# SAMV71_Xplained_Ultra_Memory.net
KiCad netlist of a schematic drawn in Altium Designer
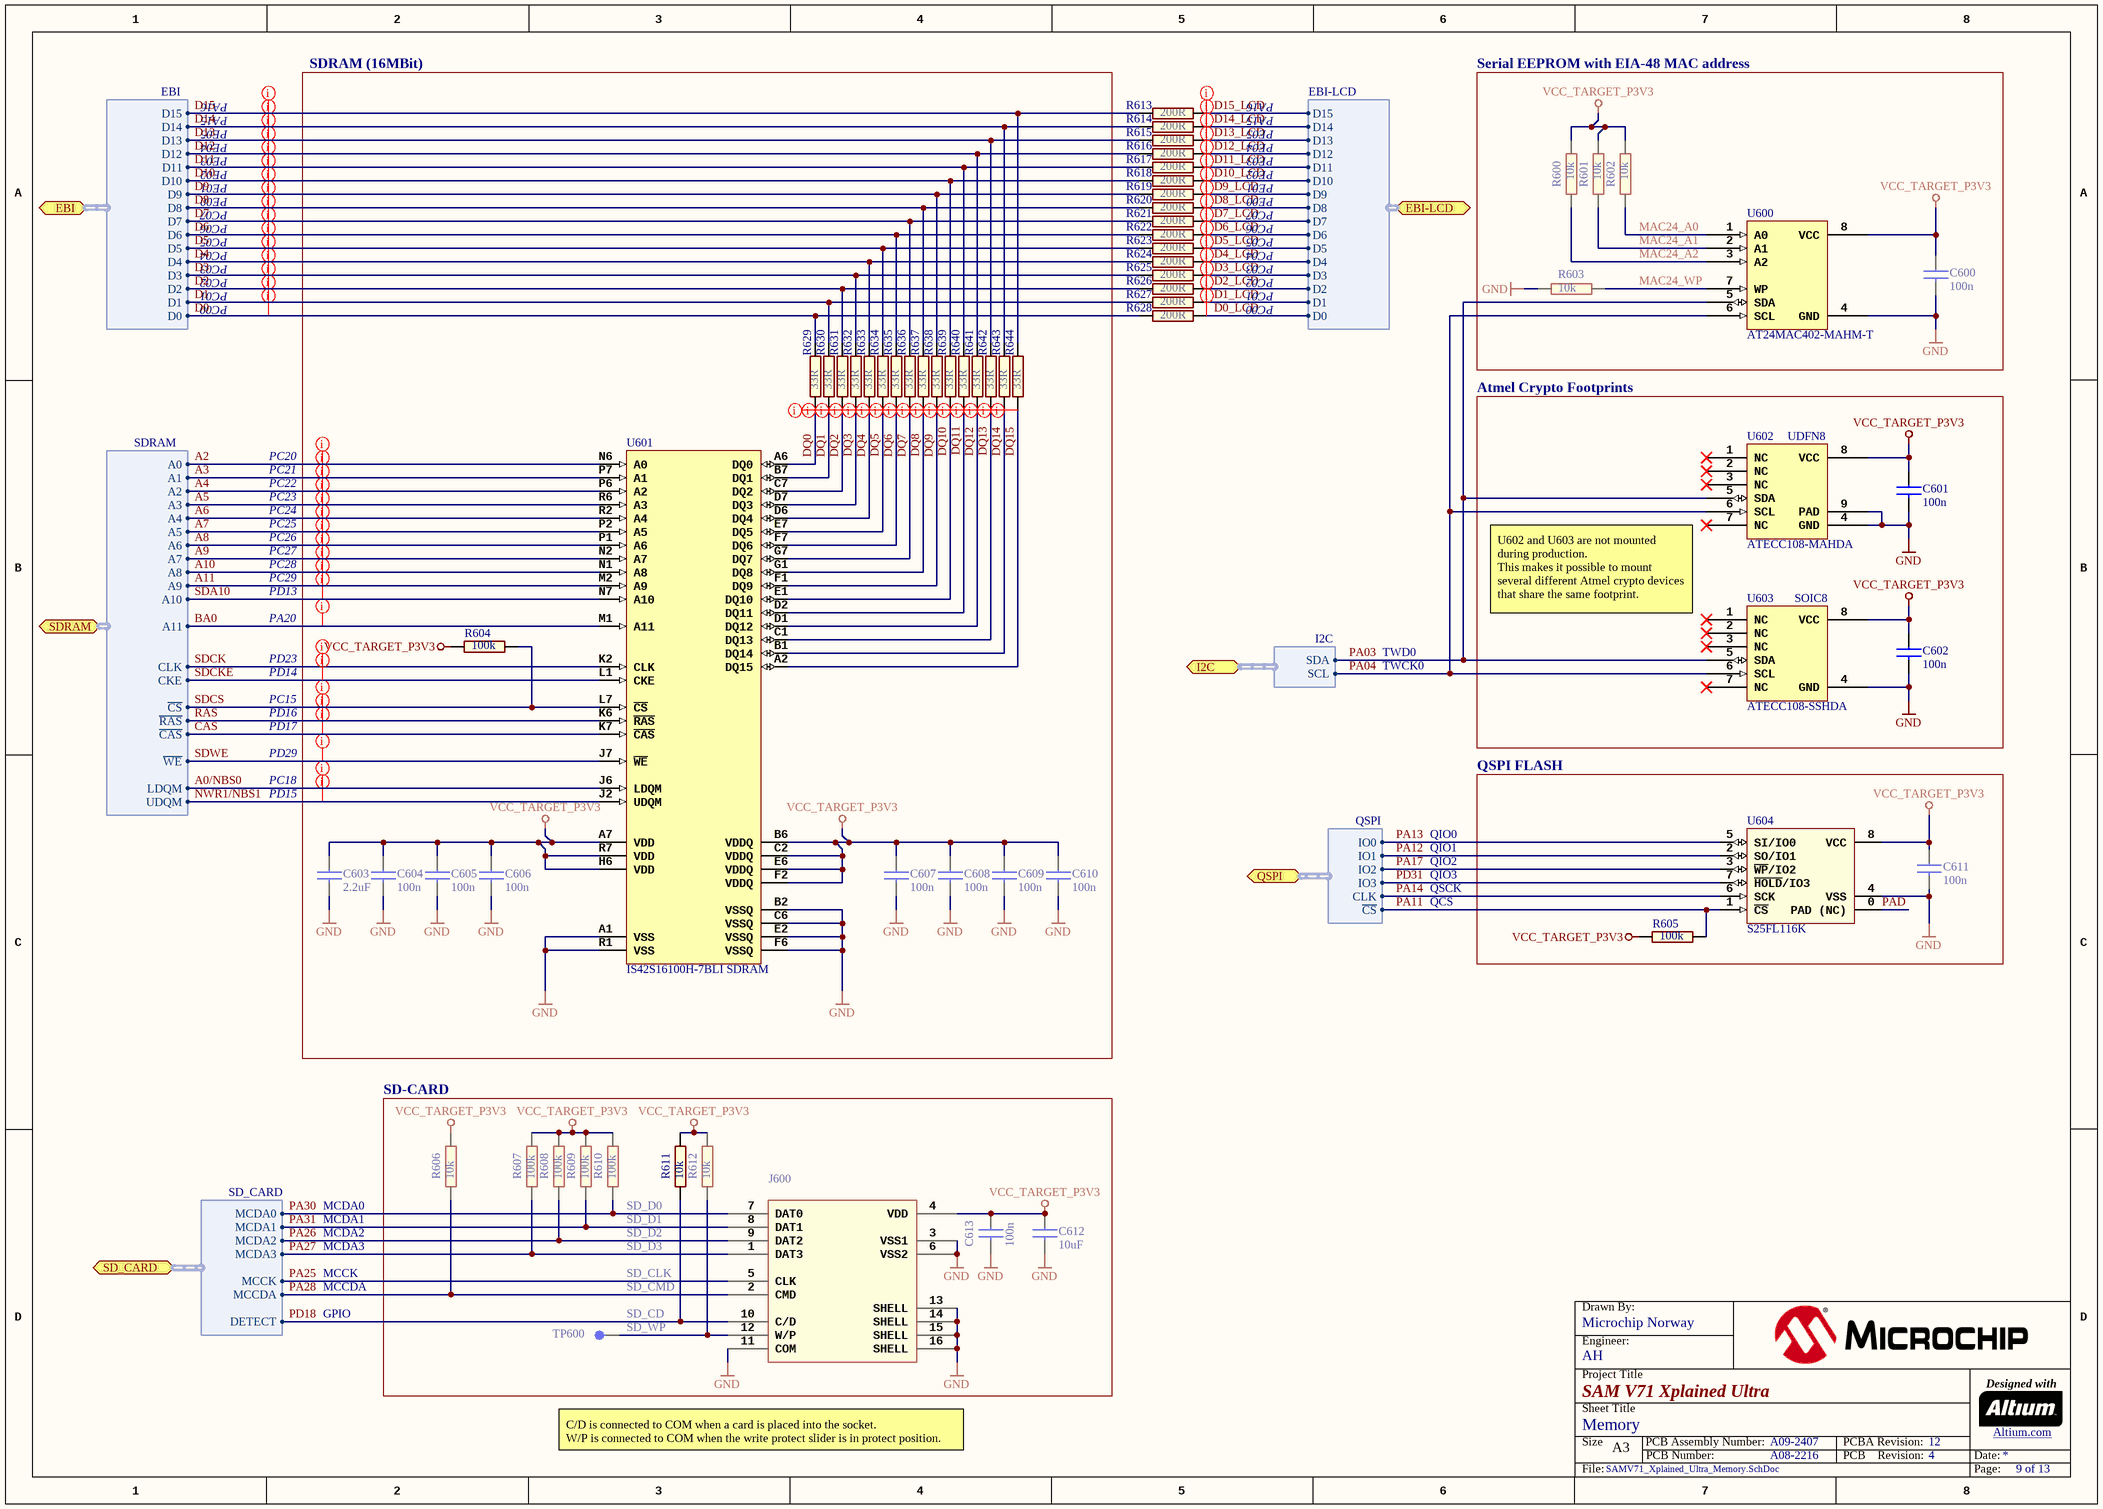
[diagram p0: SAMV71_Xplained_Ultra_Memory.SchDoc]

(export (version "E")
  (design (tool "Eeschema 10.0.6"))
  (components
    (comp (ref "C600")
      (value "100n")
      (footprint "AP1-00001")
      (description "Ceramic capacitor, SMD 0402, X7R, 16V, +/-10%")
      (fields (field (name "TOLERANCE") "16V, +/-10%") (field (name "MANUFACTURER") "Kemet"))
      (libsource (lib "AltiumDbLib") (part "CAP-NONPOL"))
    )
    (comp (ref "C601")
      (value "100n")
      (footprint "AP1-00001")
      (description "Ceramic capacitor, SMD 0402, X7R, 16V, +/-10%")
      (fields (field (name "TOLERANCE") "16V, +/-10%") (field (name "MANUFACTURER") "Kemet"))
      (libsource (lib "AltiumDbLib") (part "CAP-NONPOL"))
    )
    (comp (ref "C602")
      (value "100n")
      (footprint "AP1-00001")
      (description "Ceramic capacitor, SMD 0402, X7R, 16V, +/-10%")
      (fields (field (name "TOLERANCE") "16V, +/-10%") (field (name "MANUFACTURER") "Kemet"))
      (libsource (lib "AltiumDbLib") (part "CAP-NONPOL"))
    )
    (comp (ref "C603")
      (value "2.2uF")
      (footprint "AP1-00053")
      (description "Ceramic capacitor, SMD 0402, X5R, 6.3V, +/-20%")
      (fields (field (name "TOLERANCE") "Â±20%") (field (name "MANUFACTURER") "Kemet"))
      (libsource (lib "AltiumDbLib") (part "CAP-NONPOL"))
    )
    (comp (ref "C604")
      (value "100n")
      (footprint "AP1-00053")
      (description "Ceramic capacitor, SMD 0402, X7R, 16V, +/-10%")
      (fields (field (name "TOLERANCE") "16V, +/-10%") (field (name "MANUFACTURER") "Kemet"))
      (libsource (lib "AltiumDbLib") (part "CAP-NONPOL"))
    )
    (comp (ref "C605")
      (value "100n")
      (footprint "AP1-00053")
      (description "Ceramic capacitor, SMD 0402, X7R, 16V, +/-10%")
      (fields (field (name "TOLERANCE") "16V, +/-10%") (field (name "MANUFACTURER") "Kemet"))
      (libsource (lib "AltiumDbLib") (part "CAP-NONPOL"))
    )
    (comp (ref "C606")
      (value "100n")
      (footprint "AP1-00053")
      (description "Ceramic capacitor, SMD 0402, X7R, 16V, +/-10%")
      (fields (field (name "TOLERANCE") "16V, +/-10%") (field (name "MANUFACTURER") "Kemet"))
      (libsource (lib "AltiumDbLib") (part "CAP-NONPOL"))
    )
    (comp (ref "C607")
      (value "100n")
      (footprint "AP1-00053")
      (description "Ceramic capacitor, SMD 0402, X7R, 16V, +/-10%")
      (fields (field (name "TOLERANCE") "16V, +/-10%") (field (name "MANUFACTURER") "Kemet"))
      (libsource (lib "AltiumDbLib") (part "CAP-NONPOL"))
    )
    (comp (ref "C608")
      (value "100n")
      (footprint "AP1-00053")
      (description "Ceramic capacitor, SMD 0402, X7R, 16V, +/-10%")
      (fields (field (name "TOLERANCE") "16V, +/-10%") (field (name "MANUFACTURER") "Kemet"))
      (libsource (lib "AltiumDbLib") (part "CAP-NONPOL"))
    )
    (comp (ref "C609")
      (value "100n")
      (footprint "AP1-00053")
      (description "Ceramic capacitor, SMD 0402, X7R, 16V, +/-10%")
      (fields (field (name "TOLERANCE") "16V, +/-10%") (field (name "MANUFACTURER") "Kemet"))
      (libsource (lib "AltiumDbLib") (part "CAP-NONPOL"))
    )
    (comp (ref "C610")
      (value "100n")
      (footprint "AP1-00053")
      (description "Ceramic capacitor, SMD 0402, X7R, 16V, +/-10%")
      (fields (field (name "TOLERANCE") "16V, +/-10%") (field (name "MANUFACTURER") "Kemet"))
      (libsource (lib "AltiumDbLib") (part "CAP-NONPOL"))
    )
    (comp (ref "C611")
      (value "100n")
      (footprint "AP1-00001")
      (description "Ceramic capacitor, SMD 0402, X7R, 16V, +/-10%")
      (fields (field (name "TOLERANCE") "16V, +/-10%") (field (name "MANUFACTURER") "Kemet"))
      (libsource (lib "AltiumDbLib") (part "CAP-NONPOL"))
    )
    (comp (ref "C612")
      (value "10uF")
      (footprint "AP1-00041")
      (description "Ceramic capacitor, SMD 0805, X5R, 10V, 10 %, (de19441)")
      (fields (field (name "TOLERANCE") "10%") (field (name "MANUFACTURER") "Murata"))
      (libsource (lib "AltiumDbLib") (part "CAP-NONPOL"))
    )
    (comp (ref "C613")
      (value "100n")
      (footprint "AP1-00001")
      (description "Ceramic capacitor, SMD 0402, X7R, 16V, +/-10%")
      (fields (field (name "TOLERANCE") "16V, +/-10%") (field (name "MANUFACTURER") "Kemet"))
      (libsource (lib "AltiumDbLib") (part "CAP-NONPOL"))
    )
    (comp (ref "J600")
      (value "~")
      (footprint "AP8-00377")
      (description "SD/MMC socket, 2.7mm, push-push, SMD")
      (fields
        (field (name "MANUFACTURER") "Kyocera-elco")
        (field (name "MPN") "KYOCERA - 14 5738 009 220 859+")
      )
      (libsource (lib "AltiumDbLib") (part "SD_MMC"))
    )
    (comp (ref "R600")
      (value "10k")
      (footprint "AP2-00000")
      (description "Thick film resistor, SMD 0402, 1/16W, 1%")
      (fields (field (name "TOLERANCE") "1 %") (field (name "MANUFACTURER") "vishay"))
      (libsource (lib "AltiumDbLib") (part "R2"))
    )
    (comp (ref "R601")
      (value "10k")
      (footprint "AP2-00000")
      (description "Thick film resistor, SMD 0402, 1/16W, 1%")
      (fields (field (name "TOLERANCE") "1 %") (field (name "MANUFACTURER") "vishay"))
      (libsource (lib "AltiumDbLib") (part "R2"))
    )
    (comp (ref "R602")
      (value "10k")
      (footprint "AP2-00000")
      (description "Thick film resistor, SMD 0402, 1/16W, 1%")
      (fields (field (name "TOLERANCE") "1 %") (field (name "MANUFACTURER") "vishay"))
      (libsource (lib "AltiumDbLib") (part "R2"))
    )
    (comp (ref "R603")
      (value "10k")
      (footprint "AP2-00000")
      (description "Thick film resistor, SMD 0402, 1/16W, 1%")
      (fields (field (name "TOLERANCE") "1 %") (field (name "MANUFACTURER") "vishay"))
      (libsource (lib "") (part "R2_2"))
    )
    (comp (ref "R604")
      (value "100k")
      (footprint "AP2-00000")
      (description "Thick film resistor, SMD 0402, 1/16W, 1%")
      (fields (field (name "TOLERANCE") "1 %") (field (name "MANUFACTURER") "ASJ"))
      (libsource (lib "") (part "R2_2"))
    )
    (comp (ref "R605")
      (value "100k")
      (footprint "AP2-00000")
      (description "Thick film resistor, SMD 0402, 1/16W, 1%")
      (fields (field (name "TOLERANCE") "1 %") (field (name "MANUFACTURER") "ASJ"))
      (libsource (lib "") (part "R2_2"))
    )
    (comp (ref "R606")
      (value "10k")
      (footprint "AP2-00000")
      (description "Thick film resistor, SMD 0402, 1/16W, 1%")
      (fields (field (name "TOLERANCE") "1 %") (field (name "MANUFACTURER") "vishay"))
      (libsource (lib "AltiumDbLib") (part "R2"))
    )
    (comp (ref "R607")
      (value "100k")
      (footprint "AP2-00000")
      (description "Thick film resistor, SMD 0402, 1/16W, 1%")
      (fields (field (name "TOLERANCE") "1 %") (field (name "MANUFACTURER") "ASJ"))
      (libsource (lib "AltiumDbLib") (part "R2"))
    )
    (comp (ref "R608")
      (value "100k")
      (footprint "AP2-00000")
      (description "Thick film resistor, SMD 0402, 1/16W, 1%")
      (fields (field (name "TOLERANCE") "1 %") (field (name "MANUFACTURER") "ASJ"))
      (libsource (lib "AltiumDbLib") (part "R2"))
    )
    (comp (ref "R609")
      (value "100k")
      (footprint "AP2-00000")
      (description "Thick film resistor, SMD 0402, 1/16W, 1%")
      (fields (field (name "TOLERANCE") "1 %") (field (name "MANUFACTURER") "ASJ"))
      (libsource (lib "AltiumDbLib") (part "R2"))
    )
    (comp (ref "R610")
      (value "100k")
      (footprint "AP2-00000")
      (description "Thick film resistor, SMD 0402, 1/16W, 1%")
      (fields (field (name "TOLERANCE") "1 %") (field (name "MANUFACTURER") "ASJ"))
      (libsource (lib "AltiumDbLib") (part "R2"))
    )
    (comp (ref "R611")
      (value "10k")
      (footprint "AP2-00000")
      (description "Thick film resistor, SMD 0402, 1/16W, 1%")
      (fields (field (name "TOLERANCE") "1 %") (field (name "MANUFACTURER") "vishay"))
      (libsource (lib "AltiumDbLib") (part "R2"))
    )
    (comp (ref "R612")
      (value "10k")
      (footprint "AP2-00000")
      (description "Thick film resistor, SMD 0402, 1/16W, 1%")
      (fields (field (name "TOLERANCE") "1 %") (field (name "MANUFACTURER") "vishay"))
      (libsource (lib "AltiumDbLib") (part "R2"))
    )
    (comp (ref "R613")
      (value "200R")
      (footprint "AP2-00011")
      (description "Thick film resistor, SMD 0402, 1/16W, 1%")
      (fields (field (name "TOLERANCE") "1 %"))
      (libsource (lib "") (part "R2_1"))
    )
    (comp (ref "R614")
      (value "200R")
      (footprint "AP2-00011")
      (description "Thick film resistor, SMD 0402, 1/16W, 1%")
      (fields (field (name "TOLERANCE") "1 %"))
      (libsource (lib "") (part "R2_1"))
    )
    (comp (ref "R615")
      (value "200R")
      (footprint "AP2-00011")
      (description "Thick film resistor, SMD 0402, 1/16W, 1%")
      (fields (field (name "TOLERANCE") "1 %"))
      (libsource (lib "") (part "R2_1"))
    )
    (comp (ref "R616")
      (value "200R")
      (footprint "AP2-00011")
      (description "Thick film resistor, SMD 0402, 1/16W, 1%")
      (fields (field (name "TOLERANCE") "1 %"))
      (libsource (lib "") (part "R2_1"))
    )
    (comp (ref "R617")
      (value "200R")
      (footprint "AP2-00011")
      (description "Thick film resistor, SMD 0402, 1/16W, 1%")
      (fields (field (name "TOLERANCE") "1 %"))
      (libsource (lib "") (part "R2_1"))
    )
    (comp (ref "R618")
      (value "200R")
      (footprint "AP2-00011")
      (description "Thick film resistor, SMD 0402, 1/16W, 1%")
      (fields (field (name "TOLERANCE") "1 %"))
      (libsource (lib "") (part "R2_1"))
    )
    (comp (ref "R619")
      (value "200R")
      (footprint "AP2-00011")
      (description "Thick film resistor, SMD 0402, 1/16W, 1%")
      (fields (field (name "TOLERANCE") "1 %"))
      (libsource (lib "") (part "R2_1"))
    )
    (comp (ref "R620")
      (value "200R")
      (footprint "AP2-00011")
      (description "Thick film resistor, SMD 0402, 1/16W, 1%")
      (fields (field (name "TOLERANCE") "1 %"))
      (libsource (lib "") (part "R2_1"))
    )
    (comp (ref "R621")
      (value "200R")
      (footprint "AP2-00011")
      (description "Thick film resistor, SMD 0402, 1/16W, 1%")
      (fields (field (name "TOLERANCE") "1 %"))
      (libsource (lib "") (part "R2_1"))
    )
    (comp (ref "R622")
      (value "200R")
      (footprint "AP2-00011")
      (description "Thick film resistor, SMD 0402, 1/16W, 1%")
      (fields (field (name "TOLERANCE") "1 %"))
      (libsource (lib "") (part "R2_1"))
    )
    (comp (ref "R623")
      (value "200R")
      (footprint "AP2-00011")
      (description "Thick film resistor, SMD 0402, 1/16W, 1%")
      (fields (field (name "TOLERANCE") "1 %"))
      (libsource (lib "") (part "R2_1"))
    )
    (comp (ref "R624")
      (value "200R")
      (footprint "AP2-00011")
      (description "Thick film resistor, SMD 0402, 1/16W, 1%")
      (fields (field (name "TOLERANCE") "1 %"))
      (libsource (lib "") (part "R2_1"))
    )
    (comp (ref "R625")
      (value "200R")
      (footprint "AP2-00011")
      (description "Thick film resistor, SMD 0402, 1/16W, 1%")
      (fields (field (name "TOLERANCE") "1 %"))
      (libsource (lib "") (part "R2_1"))
    )
    (comp (ref "R626")
      (value "200R")
      (footprint "AP2-00011")
      (description "Thick film resistor, SMD 0402, 1/16W, 1%")
      (fields (field (name "TOLERANCE") "1 %"))
      (libsource (lib "") (part "R2_1"))
    )
    (comp (ref "R627")
      (value "200R")
      (footprint "AP2-00011")
      (description "Thick film resistor, SMD 0402, 1/16W, 1%")
      (fields (field (name "TOLERANCE") "1 %"))
      (libsource (lib "") (part "R2_1"))
    )
    (comp (ref "R628")
      (value "200R")
      (footprint "AP2-00011")
      (description "Thick film resistor, SMD 0402, 1/16W, 1%")
      (fields (field (name "TOLERANCE") "1 %"))
      (libsource (lib "") (part "R2_1"))
    )
    (comp (ref "R629")
      (value "33R")
      (footprint "AP2-00011")
      (description "Thick film resistor, SMD 0402, 1/16W, 1%")
      (fields (field (name "TOLERANCE") "1 %") (field (name "MANUFACTURER") "ASJ"))
      (libsource (lib "") (part "R2_3"))
    )
    (comp (ref "R630")
      (value "33R")
      (footprint "AP2-00011")
      (description "Thick film resistor, SMD 0402, 1/16W, 1%")
      (fields (field (name "TOLERANCE") "1 %") (field (name "MANUFACTURER") "ASJ"))
      (libsource (lib "") (part "R2_3"))
    )
    (comp (ref "R631")
      (value "33R")
      (footprint "AP2-00011")
      (description "Thick film resistor, SMD 0402, 1/16W, 1%")
      (fields (field (name "TOLERANCE") "1 %") (field (name "MANUFACTURER") "ASJ"))
      (libsource (lib "") (part "R2_3"))
    )
    (comp (ref "R632")
      (value "33R")
      (footprint "AP2-00011")
      (description "Thick film resistor, SMD 0402, 1/16W, 1%")
      (fields (field (name "TOLERANCE") "1 %") (field (name "MANUFACTURER") "ASJ"))
      (libsource (lib "") (part "R2_3"))
    )
    (comp (ref "R633")
      (value "33R")
      (footprint "AP2-00011")
      (description "Thick film resistor, SMD 0402, 1/16W, 1%")
      (fields (field (name "TOLERANCE") "1 %") (field (name "MANUFACTURER") "ASJ"))
      (libsource (lib "") (part "R2_3"))
    )
    (comp (ref "R634")
      (value "33R")
      (footprint "AP2-00011")
      (description "Thick film resistor, SMD 0402, 1/16W, 1%")
      (fields (field (name "TOLERANCE") "1 %") (field (name "MANUFACTURER") "ASJ"))
      (libsource (lib "") (part "R2_3"))
    )
    (comp (ref "R635")
      (value "33R")
      (footprint "AP2-00011")
      (description "Thick film resistor, SMD 0402, 1/16W, 1%")
      (fields (field (name "TOLERANCE") "1 %") (field (name "MANUFACTURER") "ASJ"))
      (libsource (lib "") (part "R2_3"))
    )
    (comp (ref "R636")
      (value "33R")
      (footprint "AP2-00011")
      (description "Thick film resistor, SMD 0402, 1/16W, 1%")
      (fields (field (name "TOLERANCE") "1 %") (field (name "MANUFACTURER") "ASJ"))
      (libsource (lib "") (part "R2_3"))
    )
    (comp (ref "R637")
      (value "33R")
      (footprint "AP2-00011")
      (description "Thick film resistor, SMD 0402, 1/16W, 1%")
      (fields (field (name "TOLERANCE") "1 %") (field (name "MANUFACTURER") "ASJ"))
      (libsource (lib "") (part "R2_3"))
    )
    (comp (ref "R638")
      (value "33R")
      (footprint "AP2-00011")
      (description "Thick film resistor, SMD 0402, 1/16W, 1%")
      (fields (field (name "TOLERANCE") "1 %") (field (name "MANUFACTURER") "ASJ"))
      (libsource (lib "") (part "R2_3"))
    )
    (comp (ref "R639")
      (value "33R")
      (footprint "AP2-00011")
      (description "Thick film resistor, SMD 0402, 1/16W, 1%")
      (fields (field (name "TOLERANCE") "1 %") (field (name "MANUFACTURER") "ASJ"))
      (libsource (lib "") (part "R2_3"))
    )
    (comp (ref "R640")
      (value "33R")
      (footprint "AP2-00011")
      (description "Thick film resistor, SMD 0402, 1/16W, 1%")
      (fields (field (name "TOLERANCE") "1 %") (field (name "MANUFACTURER") "ASJ"))
      (libsource (lib "") (part "R2_3"))
    )
    (comp (ref "R641")
      (value "33R")
      (footprint "AP2-00011")
      (description "Thick film resistor, SMD 0402, 1/16W, 1%")
      (fields (field (name "TOLERANCE") "1 %") (field (name "MANUFACTURER") "ASJ"))
      (libsource (lib "") (part "R2_3"))
    )
    (comp (ref "R642")
      (value "33R")
      (footprint "AP2-00011")
      (description "Thick film resistor, SMD 0402, 1/16W, 1%")
      (fields (field (name "TOLERANCE") "1 %") (field (name "MANUFACTURER") "ASJ"))
      (libsource (lib "") (part "R2_3"))
    )
    (comp (ref "R643")
      (value "33R")
      (footprint "AP2-00011")
      (description "Thick film resistor, SMD 0402, 1/16W, 1%")
      (fields (field (name "TOLERANCE") "1 %") (field (name "MANUFACTURER") "ASJ"))
      (libsource (lib "") (part "R2_3"))
    )
    (comp (ref "R644")
      (value "33R")
      (footprint "AP2-00011")
      (description "Thick film resistor, SMD 0402, 1/16W, 1%")
      (fields (field (name "TOLERANCE") "1 %") (field (name "MANUFACTURER") "ASJ"))
      (libsource (lib "") (part "R2_3"))
    )
    (comp (ref "TP600")
      (value "~")
      (footprint "AP8-00010")
      (description "Single SMD testpad")
      (libsource (lib "AltiumDbLib") (part "TESTPOINT"))
    )
    (comp (ref "U600")
      (value "AT24MAC402-MAHM-T")
      (footprint "AP6-00186")
      (description "2kbit I2C EEPROM, single EUI-48 MAC, 1.7-5.5V, 2x3mm UDFN (8MA2)")
      (fields (field (name "MANUFACTURER") "ATMEL"))
      (libsource (lib "AltiumDbLib") (part "AT24MAC-8PIN"))
    )
    (comp (ref "U601")
      (value "IS42S16100H-7BLI SDRAM")
      (footprint "AP6-00400")
      (description "16Mbit  SDRAM (512K Words x 16 Bits x 2 Banks), 143 MHz 3,3V")
      (fields (field (name "MANUFACTURER") "ISSI") (field (name "MPN") "IS42S16100H-7BLI"))
      (libsource (lib "AltiumDbLib") (part "IS42S16100E"))
    )
    (comp (ref "U602")
      (value "ATECC108-MAHDA")
      (footprint "AP6-00409")
      (description "Secure authentication and product validation device, EEPROM, I2C, 2.0 - 5.5V, UDFN8")
      (fields (field (name "MANUFACTURER") "ATMEL") (field (name "MPN") "ATECC108-MAHDA-T"))
      (libsource (lib "AltiumDbLib") (part "ATECC108_UDFN"))
    )
    (comp (ref "U603")
      (value "ATECC108-SSHDA")
      (footprint "AP6-00071")
      (description "Secure authentication and product validation device, EEPROM, I2C, 2.0 - 5.5V, SOIC8")
      (fields (field (name "MANUFACTURER") "ATMEL") (field (name "MPN") "ATECC108-SSHDA-T"))
      (libsource (lib "AltiumDbLib") (part "ATECC108_SOIC"))
    )
    (comp (ref "U604")
      (value "S25FL116K")
      (footprint "AP6-00402")
      (description "16 Mbit (2MB) SPI Quad I/O flash, 3.3V, 108MHz, WSON-8, industrial temperature")
      (fields (field (name "MANUFACTURER") "Spansion") (field (name "MPN") "S25FL116K0XNFI013"))
      (libsource (lib "AltiumDbLib") (part "S25FL1"))
    )
  )
  (nets
    (net (code "7") (name "/A0{slash}NBS0") (class "Default")
      (node (ref "U601") (pin "J6") (pinfunction "LDQM_J6") (pintype "input"))
    )
    (net (code "8") (name "/A2") (class "Default")
      (node (ref "U601") (pin "N6") (pinfunction "A0_N6") (pintype "input"))
    )
    (net (code "9") (name "/A3") (class "Default")
      (node (ref "U601") (pin "P7") (pinfunction "A1_P7") (pintype "input"))
    )
    (net (code "10") (name "/A4") (class "Default")
      (node (ref "U601") (pin "P6") (pinfunction "A2_P6") (pintype "input"))
    )
    (net (code "11") (name "/A5") (class "Default")
      (node (ref "U601") (pin "R6") (pinfunction "A3_R6") (pintype "input"))
    )
    (net (code "12") (name "/A6") (class "Default")
      (node (ref "U601") (pin "R2") (pinfunction "A4_R2") (pintype "input"))
    )
    (net (code "13") (name "/A7") (class "Default")
      (node (ref "U601") (pin "P2") (pinfunction "A5_P2") (pintype "input"))
    )
    (net (code "14") (name "/A8") (class "Default")
      (node (ref "U601") (pin "P1") (pinfunction "A6_P1") (pintype "input"))
    )
    (net (code "15") (name "/A9") (class "Default")
      (node (ref "U601") (pin "N2") (pinfunction "A7_N2") (pintype "input"))
    )
    (net (code "16") (name "/A10") (class "Default")
      (node (ref "U601") (pin "N1") (pinfunction "A8_N1") (pintype "input"))
    )
    (net (code "17") (name "/A11") (class "Default")
      (node (ref "U601") (pin "M2") (pinfunction "A9_M2") (pintype "input"))
    )
    (net (code "18") (name "/BA0") (class "Default")
      (node (ref "U601") (pin "M1") (pinfunction "A11_M1") (pintype "input"))
    )
    (net (code "19") (name "/CAS") (class "Default")
      (node (ref "U601") (pin "K7") (pinfunction "~{CAS}_K7") (pintype "input"))
    )
    (net (code "20") (name "/D0") (class "Default")
      (node (ref "R628") (pin "2") (pinfunction "2_2") (pintype "passive"))
      (node (ref "R629") (pin "1") (pinfunction "1_1") (pintype "passive"))
    )
    (net (code "21") (name "/D0_LCD") (class "Default")
      (node (ref "R628") (pin "1") (pinfunction "1_1") (pintype "passive"))
    )
    (net (code "22") (name "/D1") (class "Default")
      (node (ref "R627") (pin "2") (pinfunction "2_2") (pintype "passive"))
      (node (ref "R630") (pin "1") (pinfunction "1_1") (pintype "passive"))
    )
    (net (code "23") (name "/D1_LCD") (class "Default")
      (node (ref "R627") (pin "1") (pinfunction "1_1") (pintype "passive"))
    )
    (net (code "24") (name "/D2") (class "Default")
      (node (ref "R626") (pin "2") (pinfunction "2_2") (pintype "passive"))
      (node (ref "R631") (pin "1") (pinfunction "1_1") (pintype "passive"))
    )
    (net (code "25") (name "/D2_LCD") (class "Default")
      (node (ref "R626") (pin "1") (pinfunction "1_1") (pintype "passive"))
    )
    (net (code "26") (name "/D3") (class "Default")
      (node (ref "R625") (pin "2") (pinfunction "2_2") (pintype "passive"))
      (node (ref "R632") (pin "1") (pinfunction "1_1") (pintype "passive"))
    )
    (net (code "27") (name "/D3_LCD") (class "Default")
      (node (ref "R625") (pin "1") (pinfunction "1_1") (pintype "passive"))
    )
    (net (code "28") (name "/D4") (class "Default")
      (node (ref "R624") (pin "2") (pinfunction "2_2") (pintype "passive"))
      (node (ref "R633") (pin "1") (pinfunction "1_1") (pintype "passive"))
    )
    (net (code "29") (name "/D4_LCD") (class "Default")
      (node (ref "R624") (pin "1") (pinfunction "1_1") (pintype "passive"))
    )
    (net (code "30") (name "/D5") (class "Default")
      (node (ref "R623") (pin "2") (pinfunction "2_2") (pintype "passive"))
      (node (ref "R634") (pin "1") (pinfunction "1_1") (pintype "passive"))
    )
    (net (code "31") (name "/D5_LCD") (class "Default")
      (node (ref "R623") (pin "1") (pinfunction "1_1") (pintype "passive"))
    )
    (net (code "32") (name "/D6") (class "Default")
      (node (ref "R622") (pin "2") (pinfunction "2_2") (pintype "passive"))
      (node (ref "R635") (pin "1") (pinfunction "1_1") (pintype "passive"))
    )
    (net (code "33") (name "/D6_LCD") (class "Default")
      (node (ref "R622") (pin "1") (pinfunction "1_1") (pintype "passive"))
    )
    (net (code "34") (name "/D7") (class "Default")
      (node (ref "R621") (pin "2") (pinfunction "2_2") (pintype "passive"))
      (node (ref "R636") (pin "1") (pinfunction "1_1") (pintype "passive"))
    )
    (net (code "35") (name "/D7_LCD") (class "Default")
      (node (ref "R621") (pin "1") (pinfunction "1_1") (pintype "passive"))
    )
    (net (code "36") (name "/D8") (class "Default")
      (node (ref "R620") (pin "2") (pinfunction "2_2") (pintype "passive"))
      (node (ref "R637") (pin "1") (pinfunction "1_1") (pintype "passive"))
    )
    (net (code "37") (name "/D8_LCD") (class "Default")
      (node (ref "R620") (pin "1") (pinfunction "1_1") (pintype "passive"))
    )
    (net (code "38") (name "/D9") (class "Default")
      (node (ref "R619") (pin "2") (pinfunction "2_2") (pintype "passive"))
      (node (ref "R638") (pin "1") (pinfunction "1_1") (pintype "passive"))
    )
    (net (code "39") (name "/D9_LCD") (class "Default")
      (node (ref "R619") (pin "1") (pinfunction "1_1") (pintype "passive"))
    )
    (net (code "40") (name "/D10") (class "Default")
      (node (ref "R618") (pin "2") (pinfunction "2_2") (pintype "passive"))
      (node (ref "R639") (pin "1") (pinfunction "1_1") (pintype "passive"))
    )
    (net (code "41") (name "/D10_LCD") (class "Default")
      (node (ref "R618") (pin "1") (pinfunction "1_1") (pintype "passive"))
    )
    (net (code "42") (name "/D11") (class "Default")
      (node (ref "R617") (pin "2") (pinfunction "2_2") (pintype "passive"))
      (node (ref "R640") (pin "1") (pinfunction "1_1") (pintype "passive"))
    )
    (net (code "43") (name "/D11_LCD") (class "Default")
      (node (ref "R617") (pin "1") (pinfunction "1_1") (pintype "passive"))
    )
    (net (code "44") (name "/D12") (class "Default")
      (node (ref "R616") (pin "2") (pinfunction "2_2") (pintype "passive"))
      (node (ref "R641") (pin "1") (pinfunction "1_1") (pintype "passive"))
    )
    (net (code "45") (name "/D12_LCD") (class "Default")
      (node (ref "R616") (pin "1") (pinfunction "1_1") (pintype "passive"))
    )
    (net (code "46") (name "/D13") (class "Default")
      (node (ref "R615") (pin "2") (pinfunction "2_2") (pintype "passive"))
      (node (ref "R642") (pin "1") (pinfunction "1_1") (pintype "passive"))
    )
    (net (code "47") (name "/D13_LCD") (class "Default")
      (node (ref "R615") (pin "1") (pinfunction "1_1") (pintype "passive"))
    )
    (net (code "48") (name "/D14") (class "Default")
      (node (ref "R614") (pin "2") (pinfunction "2_2") (pintype "passive"))
      (node (ref "R643") (pin "1") (pinfunction "1_1") (pintype "passive"))
    )
    (net (code "49") (name "/D14_LCD") (class "Default")
      (node (ref "R614") (pin "1") (pinfunction "1_1") (pintype "passive"))
    )
    (net (code "50") (name "/D15") (class "Default")
      (node (ref "R613") (pin "2") (pinfunction "2_2") (pintype "passive"))
      (node (ref "R644") (pin "1") (pinfunction "1_1") (pintype "passive"))
    )
    (net (code "51") (name "/D15_LCD") (class "Default")
      (node (ref "R613") (pin "1") (pinfunction "1_1") (pintype "passive"))
    )
    (net (code "52") (name "/DQ0") (class "Default")
      (node (ref "R629") (pin "2") (pinfunction "2_2") (pintype "passive"))
      (node (ref "U601") (pin "A6") (pinfunction "DQ0_A6") (pintype "bidirectional"))
    )
    (net (code "53") (name "/DQ1") (class "Default")
      (node (ref "R630") (pin "2") (pinfunction "2_2") (pintype "passive"))
      (node (ref "U601") (pin "B7") (pinfunction "DQ1_B7") (pintype "bidirectional"))
    )
    (net (code "54") (name "/DQ2") (class "Default")
      (node (ref "R631") (pin "2") (pinfunction "2_2") (pintype "passive"))
      (node (ref "U601") (pin "C7") (pinfunction "DQ2_C7") (pintype "bidirectional"))
    )
    (net (code "55") (name "/DQ3") (class "Default")
      (node (ref "R632") (pin "2") (pinfunction "2_2") (pintype "passive"))
      (node (ref "U601") (pin "D7") (pinfunction "DQ3_D7") (pintype "bidirectional"))
    )
    (net (code "56") (name "/DQ4") (class "Default")
      (node (ref "R633") (pin "2") (pinfunction "2_2") (pintype "passive"))
      (node (ref "U601") (pin "D6") (pinfunction "DQ4_D6") (pintype "bidirectional"))
    )
    (net (code "57") (name "/DQ5") (class "Default")
      (node (ref "R634") (pin "2") (pinfunction "2_2") (pintype "passive"))
      (node (ref "U601") (pin "E7") (pinfunction "DQ5_E7") (pintype "bidirectional"))
    )
    (net (code "58") (name "/DQ6") (class "Default")
      (node (ref "R635") (pin "2") (pinfunction "2_2") (pintype "passive"))
      (node (ref "U601") (pin "F7") (pinfunction "DQ6_F7") (pintype "bidirectional"))
    )
    (net (code "59") (name "/DQ7") (class "Default")
      (node (ref "R636") (pin "2") (pinfunction "2_2") (pintype "passive"))
      (node (ref "U601") (pin "G7") (pinfunction "DQ7_G7") (pintype "bidirectional"))
    )
    (net (code "60") (name "/DQ8") (class "Default")
      (node (ref "R637") (pin "2") (pinfunction "2_2") (pintype "passive"))
      (node (ref "U601") (pin "G1") (pinfunction "DQ8_G1") (pintype "bidirectional"))
    )
    (net (code "61") (name "/DQ9") (class "Default")
      (node (ref "R638") (pin "2") (pinfunction "2_2") (pintype "passive"))
      (node (ref "U601") (pin "F1") (pinfunction "DQ9_F1") (pintype "bidirectional"))
    )
    (net (code "62") (name "/DQ10") (class "Default")
      (node (ref "R639") (pin "2") (pinfunction "2_2") (pintype "passive"))
      (node (ref "U601") (pin "E1") (pinfunction "DQ10_E1") (pintype "bidirectional"))
    )
    (net (code "63") (name "/DQ11") (class "Default")
      (node (ref "R640") (pin "2") (pinfunction "2_2") (pintype "passive"))
      (node (ref "U601") (pin "D2") (pinfunction "DQ11_D2") (pintype "bidirectional"))
    )
    (net (code "64") (name "/DQ12") (class "Default")
      (node (ref "R641") (pin "2") (pinfunction "2_2") (pintype "passive"))
      (node (ref "U601") (pin "D1") (pinfunction "DQ12_D1") (pintype "bidirectional"))
    )
    (net (code "65") (name "/DQ13") (class "Default")
      (node (ref "R642") (pin "2") (pinfunction "2_2") (pintype "passive"))
      (node (ref "U601") (pin "C1") (pinfunction "DQ13_C1") (pintype "bidirectional"))
    )
    (net (code "66") (name "/DQ14") (class "Default")
      (node (ref "R643") (pin "2") (pinfunction "2_2") (pintype "passive"))
      (node (ref "U601") (pin "B1") (pinfunction "DQ14_B1") (pintype "bidirectional"))
    )
    (net (code "67") (name "/DQ15") (class "Default")
      (node (ref "R644") (pin "2") (pinfunction "2_2") (pintype "passive"))
      (node (ref "U601") (pin "A2") (pinfunction "DQ15_A2") (pintype "bidirectional"))
    )
    (net (code "68") (name "/MAC24_A0") (class "Default")
      (node (ref "R602") (pin "1") (pinfunction "1_1") (pintype "passive"))
      (node (ref "U600") (pin "1") (pinfunction "A0_1") (pintype "input"))
    )
    (net (code "69") (name "/MAC24_A1") (class "Default")
      (node (ref "R601") (pin "1") (pinfunction "1_1") (pintype "passive"))
      (node (ref "U600") (pin "2") (pinfunction "A1_2") (pintype "input"))
    )
    (net (code "70") (name "/MAC24_A2") (class "Default")
      (node (ref "R600") (pin "1") (pinfunction "1_1") (pintype "passive"))
      (node (ref "U600") (pin "3") (pinfunction "A2_3") (pintype "input"))
    )
    (net (code "71") (name "/MAC24_WP") (class "Default")
      (node (ref "R603") (pin "2") (pinfunction "2_2") (pintype "passive"))
      (node (ref "U600") (pin "7") (pinfunction "WP_7") (pintype "input"))
    )
    (net (code "72") (name "/NWR1{slash}NBS1") (class "Default")
      (node (ref "U601") (pin "J2") (pinfunction "UDQM_J2") (pintype "input"))
    )
    (net (code "73") (name "/PA03") (class "Default")
      (node (ref "U600") (pin "5") (pinfunction "SDA_5") (pintype "bidirectional"))
      (node (ref "U602") (pin "5") (pinfunction "SDA_5") (pintype "bidirectional"))
      (node (ref "U603") (pin "5") (pinfunction "SDA_5") (pintype "bidirectional"))
    )
    (net (code "74") (name "/PA04") (class "Default")
      (node (ref "U600") (pin "6") (pinfunction "SCL_6") (pintype "input"))
      (node (ref "U602") (pin "6") (pinfunction "SCL_6") (pintype "input"))
      (node (ref "U603") (pin "6") (pinfunction "SCL_6") (pintype "input"))
    )
    (net (code "75") (name "/PA11") (class "Default")
      (node (ref "R605") (pin "2") (pinfunction "2_2") (pintype "passive"))
      (node (ref "U604") (pin "1") (pinfunction "~{CS}_1") (pintype "input"))
    )
    (net (code "76") (name "/PA12") (class "Default")
      (node (ref "U604") (pin "2") (pinfunction "SO/IO1_2") (pintype "bidirectional"))
    )
    (net (code "77") (name "/PA13") (class "Default")
      (node (ref "U604") (pin "5") (pinfunction "SI/IO0_5") (pintype "bidirectional"))
    )
    (net (code "78") (name "/PA14") (class "Default")
      (node (ref "U604") (pin "6") (pinfunction "SCK_6") (pintype "input"))
    )
    (net (code "79") (name "/PA17") (class "Default")
      (node (ref "U604") (pin "3") (pinfunction "~{WP}/IO2_3") (pintype "bidirectional"))
    )
    (net (code "80") (name "/PA25") (class "Default")
      (node (ref "J600") (pin "5") (pinfunction "CLK_5") (pintype "passive"))
    )
    (net (code "81") (name "/PA26") (class "Default")
      (node (ref "J600") (pin "9") (pinfunction "DAT2_9") (pintype "passive"))
      (node (ref "R608") (pin "1") (pinfunction "1_1") (pintype "passive"))
    )
    (net (code "82") (name "/PA27") (class "Default")
      (node (ref "J600") (pin "1") (pinfunction "DAT3_1") (pintype "passive"))
      (node (ref "R607") (pin "1") (pinfunction "1_1") (pintype "passive"))
    )
    (net (code "83") (name "/PA28") (class "Default")
      (node (ref "J600") (pin "2") (pinfunction "CMD_2") (pintype "passive"))
      (node (ref "R606") (pin "1") (pinfunction "1_1") (pintype "passive"))
    )
    (net (code "84") (name "/PA30") (class "Default")
      (node (ref "J600") (pin "7") (pinfunction "DAT0_7") (pintype "passive"))
      (node (ref "R610") (pin "1") (pinfunction "1_1") (pintype "passive"))
    )
    (net (code "85") (name "/PA31") (class "Default")
      (node (ref "J600") (pin "8") (pinfunction "DAT1_8") (pintype "passive"))
      (node (ref "R609") (pin "1") (pinfunction "1_1") (pintype "passive"))
    )
    (net (code "86") (name "/PAD") (class "Default")
      (node (ref "U604") (pin "0") (pinfunction "PAD_(NC)_0") (pintype "power_in"))
    )
    (net (code "87") (name "/PD18") (class "Default")
      (node (ref "J600") (pin "10") (pinfunction "C/D_10") (pintype "passive"))
      (node (ref "R611") (pin "1") (pinfunction "1_1") (pintype "passive"))
    )
    (net (code "88") (name "/PD31") (class "Default")
      (node (ref "U604") (pin "7") (pinfunction "~{HOLD}/IO3_7") (pintype "bidirectional"))
    )
    (net (code "89") (name "/RAS") (class "Default")
      (node (ref "U601") (pin "K6") (pinfunction "~{RAS}_K6") (pintype "input"))
    )
    (net (code "90") (name "/SDA10") (class "Default")
      (node (ref "U601") (pin "N7") (pinfunction "A10_N7") (pintype "input"))
    )
    (net (code "91") (name "/SDCK") (class "Default")
      (node (ref "U601") (pin "K2") (pinfunction "CLK_K2") (pintype "input"))
    )
    (net (code "92") (name "/SDCKE") (class "Default")
      (node (ref "U601") (pin "L1") (pinfunction "CKE_L1") (pintype "input"))
    )
    (net (code "93") (name "/SDCS") (class "Default")
      (node (ref "R604") (pin "2") (pinfunction "2_2") (pintype "passive"))
      (node (ref "U601") (pin "L7") (pinfunction "~{CS}_L7") (pintype "input"))
    )
    (net (code "94") (name "/SDWE") (class "Default")
      (node (ref "U601") (pin "J7") (pinfunction "~{WE}_J7") (pintype "input"))
    )
    (net (code "101") (name "GND") (class "Default")
      (node (ref "C600") (pin "2") (pinfunction "2_2") (pintype "passive"))
      (node (ref "C601") (pin "2") (pinfunction "2_2") (pintype "passive"))
      (node (ref "C602") (pin "2") (pinfunction "2_2") (pintype "passive"))
      (node (ref "C603") (pin "2") (pinfunction "2_2") (pintype "passive"))
      (node (ref "C604") (pin "2") (pinfunction "2_2") (pintype "passive"))
      (node (ref "C605") (pin "2") (pinfunction "2_2") (pintype "passive"))
      (node (ref "C606") (pin "2") (pinfunction "2_2") (pintype "passive"))
      (node (ref "C607") (pin "2") (pinfunction "2_2") (pintype "passive"))
      (node (ref "C608") (pin "2") (pinfunction "2_2") (pintype "passive"))
      (node (ref "C609") (pin "2") (pinfunction "2_2") (pintype "passive"))
      (node (ref "C610") (pin "2") (pinfunction "2_2") (pintype "passive"))
      (node (ref "C611") (pin "2") (pinfunction "2_2") (pintype "passive"))
      (node (ref "C612") (pin "2") (pinfunction "2_2") (pintype "passive"))
      (node (ref "C613") (pin "2") (pinfunction "2_2") (pintype "passive"))
      (node (ref "J600") (pin "11") (pinfunction "COM_11") (pintype "passive"))
      (node (ref "J600") (pin "13") (pinfunction "SHELL_13") (pintype "passive"))
      (node (ref "J600") (pin "14") (pinfunction "SHELL_14") (pintype "passive"))
      (node (ref "J600") (pin "15") (pinfunction "SHELL_15") (pintype "passive"))
      (node (ref "J600") (pin "16") (pinfunction "SHELL_16") (pintype "passive"))
      (node (ref "J600") (pin "3") (pinfunction "VSS1_3") (pintype "passive"))
      (node (ref "J600") (pin "6") (pinfunction "VSS2_6") (pintype "passive"))
      (node (ref "R603") (pin "1") (pinfunction "1_1") (pintype "passive"))
      (node (ref "U600") (pin "4") (pinfunction "GND_4") (pintype "power_in"))
      (node (ref "U601") (pin "A1") (pinfunction "VSS_A1") (pintype "power_in"))
      (node (ref "U601") (pin "B2") (pinfunction "VSSQ_B2") (pintype "power_in"))
      (node (ref "U601") (pin "C6") (pinfunction "VSSQ_C6") (pintype "power_in"))
      (node (ref "U601") (pin "E2") (pinfunction "VSSQ_E2") (pintype "power_in"))
      (node (ref "U601") (pin "F6") (pinfunction "VSSQ_F6") (pintype "power_in"))
      (node (ref "U601") (pin "R1") (pinfunction "VSS_R1") (pintype "power_in"))
      (node (ref "U602") (pin "4") (pinfunction "GND_4") (pintype "power_in"))
      (node (ref "U602") (pin "9") (pinfunction "PAD_9") (pintype "power_in"))
      (node (ref "U603") (pin "4") (pinfunction "GND_4") (pintype "power_in"))
      (node (ref "U604") (pin "4") (pinfunction "VSS_4") (pintype "power_in"))
    )
    (net (code "102") (name "Net-(J600-W{slash}P)") (class "Default")
      (node (ref "J600") (pin "12") (pinfunction "W/P_12") (pintype "passive"))
      (node (ref "R612") (pin "1") (pinfunction "1_1") (pintype "passive"))
      (node (ref "TP600") (pin "1") (pinfunction "1_1") (pintype "passive"))
    )
    (net (code "103") (name "VCC_TARGET_P3V3") (class "Default")
      (node (ref "C600") (pin "1") (pinfunction "1_1") (pintype "passive"))
      (node (ref "C601") (pin "1") (pinfunction "1_1") (pintype "passive"))
      (node (ref "C602") (pin "1") (pinfunction "1_1") (pintype "passive"))
      (node (ref "C603") (pin "1") (pinfunction "1_1") (pintype "passive"))
      (node (ref "C604") (pin "1") (pinfunction "1_1") (pintype "passive"))
      (node (ref "C605") (pin "1") (pinfunction "1_1") (pintype "passive"))
      (node (ref "C606") (pin "1") (pinfunction "1_1") (pintype "passive"))
      (node (ref "C607") (pin "1") (pinfunction "1_1") (pintype "passive"))
      (node (ref "C608") (pin "1") (pinfunction "1_1") (pintype "passive"))
      (node (ref "C609") (pin "1") (pinfunction "1_1") (pintype "passive"))
      (node (ref "C610") (pin "1") (pinfunction "1_1") (pintype "passive"))
      (node (ref "C611") (pin "1") (pinfunction "1_1") (pintype "passive"))
      (node (ref "C612") (pin "1") (pinfunction "1_1") (pintype "passive"))
      (node (ref "C613") (pin "1") (pinfunction "1_1") (pintype "passive"))
      (node (ref "J600") (pin "4") (pinfunction "VDD_4") (pintype "passive"))
      (node (ref "R600") (pin "2") (pinfunction "2_2") (pintype "passive"))
      (node (ref "R601") (pin "2") (pinfunction "2_2") (pintype "passive"))
      (node (ref "R602") (pin "2") (pinfunction "2_2") (pintype "passive"))
      (node (ref "R604") (pin "1") (pinfunction "1_1") (pintype "passive"))
      (node (ref "R605") (pin "1") (pinfunction "1_1") (pintype "passive"))
      (node (ref "R606") (pin "2") (pinfunction "2_2") (pintype "passive"))
      (node (ref "R607") (pin "2") (pinfunction "2_2") (pintype "passive"))
      (node (ref "R608") (pin "2") (pinfunction "2_2") (pintype "passive"))
      (node (ref "R609") (pin "2") (pinfunction "2_2") (pintype "passive"))
      (node (ref "R610") (pin "2") (pinfunction "2_2") (pintype "passive"))
      (node (ref "R611") (pin "2") (pinfunction "2_2") (pintype "passive"))
      (node (ref "R612") (pin "2") (pinfunction "2_2") (pintype "passive"))
      (node (ref "U600") (pin "8") (pinfunction "VCC_8") (pintype "power_in"))
      (node (ref "U601") (pin "A7") (pinfunction "VDD_A7") (pintype "power_in"))
      (node (ref "U601") (pin "B6") (pinfunction "VDDQ_B6") (pintype "power_in"))
      (node (ref "U601") (pin "C2") (pinfunction "VDDQ_C2") (pintype "power_in"))
      (node (ref "U601") (pin "E6") (pinfunction "VDDQ_E6") (pintype "power_in"))
      (node (ref "U601") (pin "F2") (pinfunction "VDDQ_F2") (pintype "power_in"))
      (node (ref "U601") (pin "H6") (pinfunction "VDD_H6") (pintype "power_in"))
      (node (ref "U601") (pin "R7") (pinfunction "VDD_R7") (pintype "power_in"))
      (node (ref "U602") (pin "8") (pinfunction "VCC_8") (pintype "power_in"))
      (node (ref "U603") (pin "8") (pinfunction "VCC_8") (pintype "power_in"))
      (node (ref "U604") (pin "8") (pinfunction "VCC_8") (pintype "power_in"))
    )
    (net (code "104") (name "unconnected-(U602-NC-Pad1)") (class "Default")
      (node (ref "U602") (pin "1") (pinfunction "NC_1") (pintype "passive+no_connect"))
    )
    (net (code "105") (name "unconnected-(U602-NC-Pad2)") (class "Default")
      (node (ref "U602") (pin "2") (pinfunction "NC_2") (pintype "passive+no_connect"))
    )
    (net (code "106") (name "unconnected-(U602-NC-Pad3)") (class "Default")
      (node (ref "U602") (pin "3") (pinfunction "NC_3") (pintype "passive+no_connect"))
    )
    (net (code "107") (name "unconnected-(U602-NC-Pad7)") (class "Default")
      (node (ref "U602") (pin "7") (pinfunction "NC_7") (pintype "passive+no_connect"))
    )
    (net (code "108") (name "unconnected-(U603-NC-Pad1)") (class "Default")
      (node (ref "U603") (pin "1") (pinfunction "NC_1") (pintype "passive+no_connect"))
    )
    (net (code "109") (name "unconnected-(U603-NC-Pad2)") (class "Default")
      (node (ref "U603") (pin "2") (pinfunction "NC_2") (pintype "passive+no_connect"))
    )
    (net (code "110") (name "unconnected-(U603-NC-Pad3)") (class "Default")
      (node (ref "U603") (pin "3") (pinfunction "NC_3") (pintype "passive+no_connect"))
    )
    (net (code "111") (name "unconnected-(U603-NC-Pad7)") (class "Default")
      (node (ref "U603") (pin "7") (pinfunction "NC_7") (pintype "passive+no_connect"))
    )
  )
)
